# 4-USB_SATA.net
KiCad netlist of a schematic drawn in Altium Designer
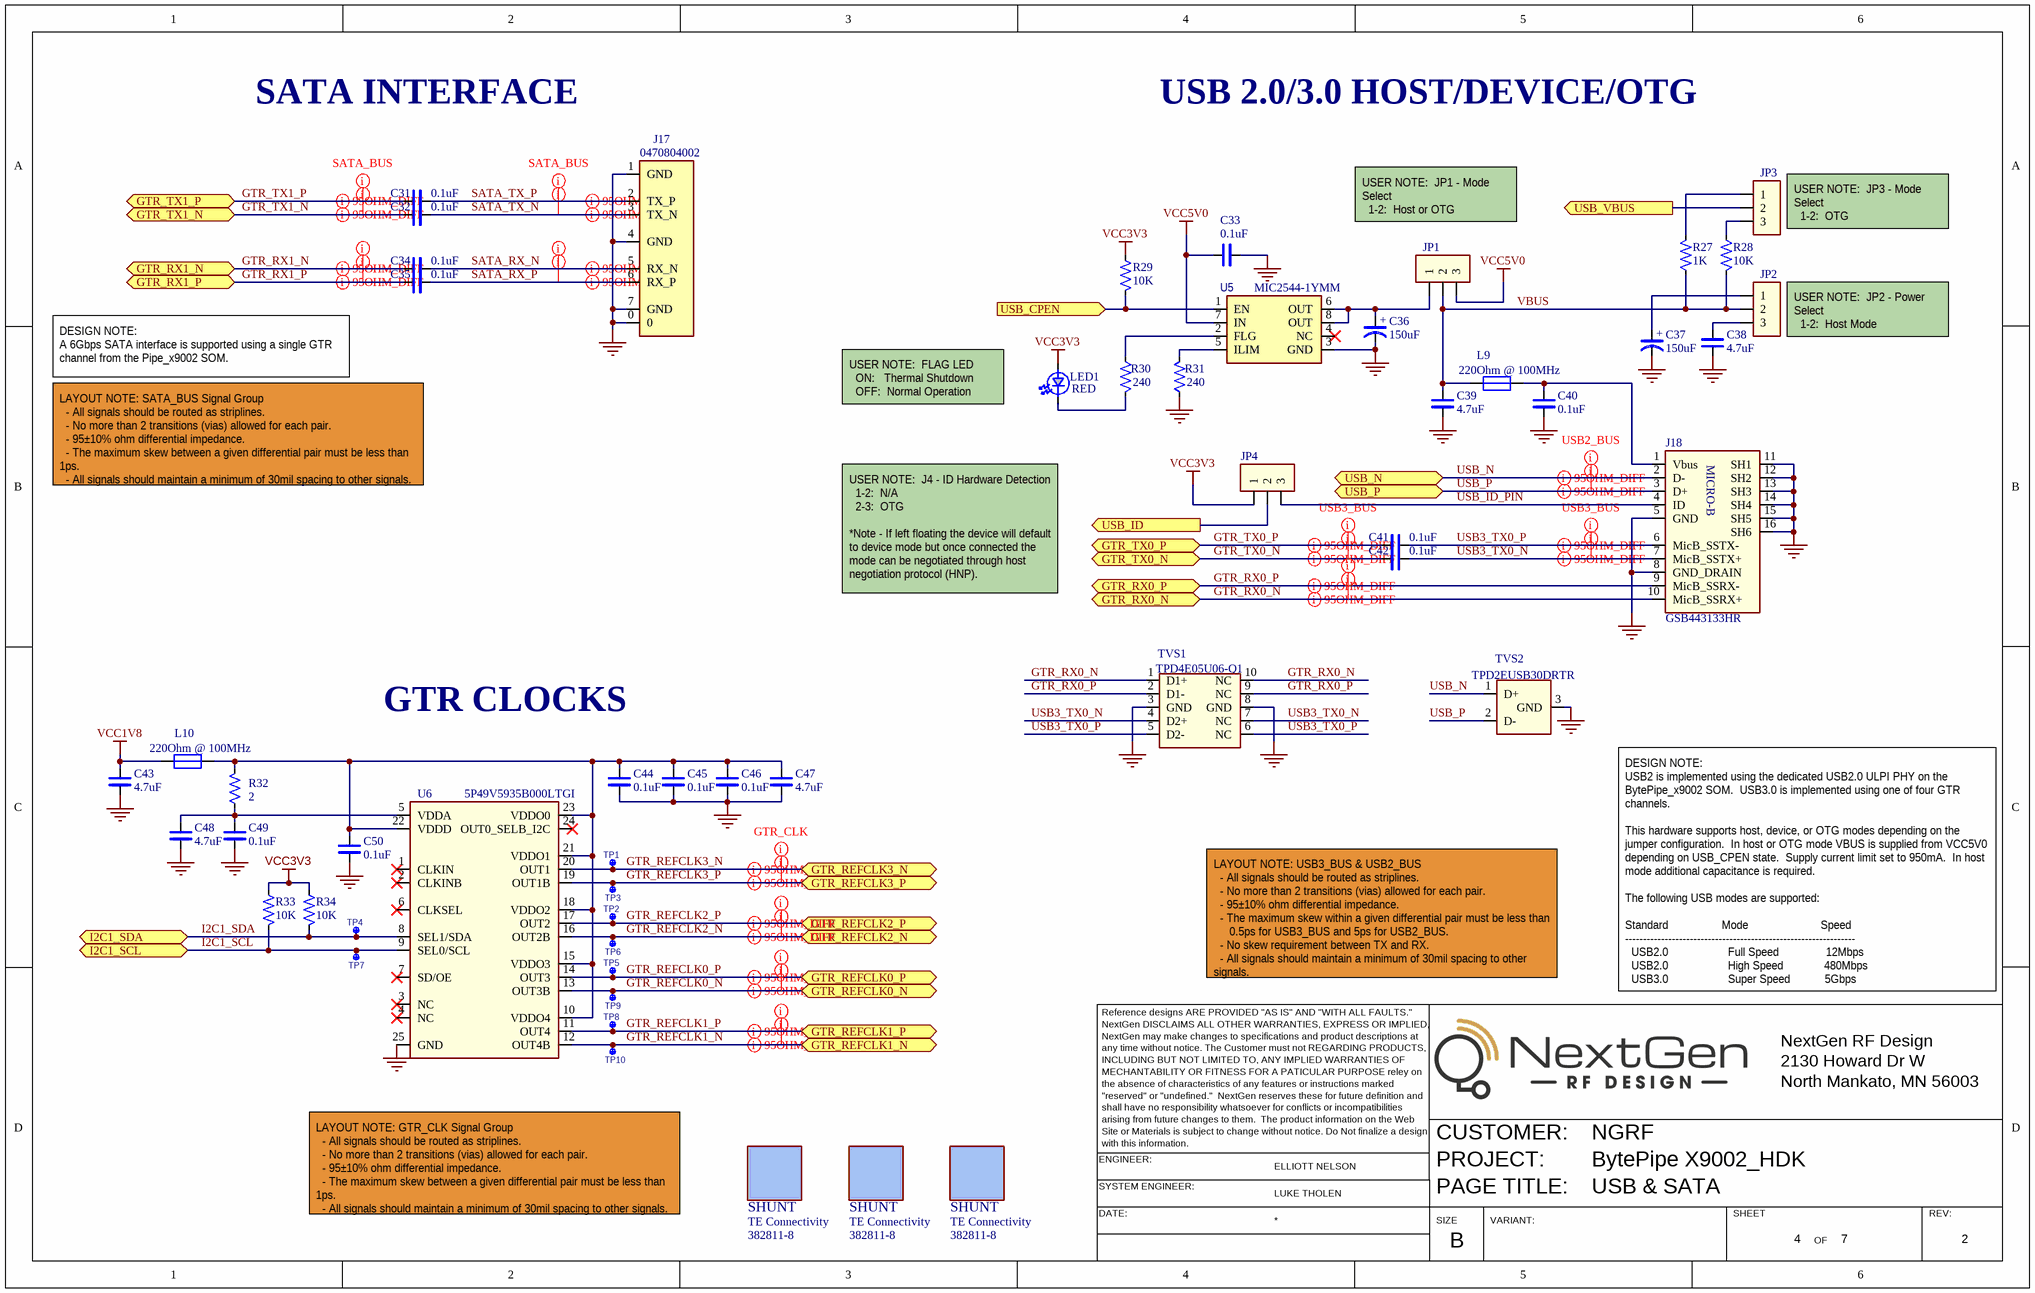
[diagram p0: 4-USB & SATA.SchDoc]

(export (version "E")
  (design (tool "Eeschema 10.0.6"))
  (components
    (comp (ref "C31")
      (value "0.1uF")
      (footprint "SM/0402/CAP")
      (description "CAP CER 0.1UF 25V X7R 0402")
      (fields (field (name "Comment") "CAP_CERAMIC_0402"))
      (libsource (lib "NextGenRF_Symbols_SMT") (part "CAP_CERAMIC_0402"))
    )
    (comp (ref "C32")
      (value "0.1uF")
      (footprint "SM/0402/CAP")
      (description "CAP CER 0.1UF 25V X7R 0402")
      (fields (field (name "Comment") "CAP_CERAMIC_0402"))
      (libsource (lib "NextGenRF_Symbols_SMT") (part "CAP_CERAMIC_0402"))
    )
    (comp (ref "C33")
      (value "0.1uF")
      (footprint "SM/0402/CAP")
      (description "CAP CER 0.1UF 25V X7R 0402")
      (fields (field (name "Comment") "CAP_CERAMIC_0402"))
      (libsource (lib "NextGenRF_Symbols_SMT") (part "CAP_CERAMIC_0402"))
    )
    (comp (ref "C34")
      (value "0.1uF")
      (footprint "SM/0402/CAP")
      (description "CAP CER 0.1UF 25V X7R 0402")
      (fields (field (name "Comment") "CAP_CERAMIC_0402"))
      (libsource (lib "NextGenRF_Symbols_SMT") (part "CAP_CERAMIC_0402"))
    )
    (comp (ref "C35")
      (value "0.1uF")
      (footprint "SM/0402/CAP")
      (description "CAP CER 0.1UF 25V X7R 0402")
      (fields (field (name "Comment") "CAP_CERAMIC_0402"))
      (libsource (lib "NextGenRF_Symbols_SMT") (part "CAP_CERAMIC_0402"))
    )
    (comp (ref "C36")
      (value "150uF")
      (footprint "NGRF_SMT_Footprints:SM/CAP/TANT-D_A")
      (description "CAP TANT 150UF 20% 10V 2917")
      (fields (field (name "Comment") "TANT-D"))
      (libsource (lib "NextGenRF_Symbols_SMT") (part "CAP_TANT-D"))
    )
    (comp (ref "C37")
      (value "150uF")
      (footprint "NGRF_SMT_Footprints:SM/CAP/TANT-D_A")
      (description "CAP TANT 150UF 20% 10V 2917")
      (fields (field (name "Comment") "TANT-D"))
      (libsource (lib "NextGenRF_Symbols_SMT") (part "CAP_TANT-D"))
    )
    (comp (ref "C38")
      (value "4.7uF")
      (footprint "SM/0402/CAP")
      (description "CAP CER 4.7UF 10V X5R 0402")
      (fields (field (name "Comment") "CAP_CERAMIC_0402"))
      (libsource (lib "NextGenRF_Symbols_SMT") (part "CAP_CERAMIC_0402"))
    )
    (comp (ref "C39")
      (value "4.7uF")
      (footprint "SM/0402/CAP")
      (description "CAP CER 4.7UF 10V X5R 0402")
      (fields (field (name "Comment") "CAP_CERAMIC_0402"))
      (libsource (lib "NextGenRF_Symbols_SMT") (part "CAP_CERAMIC_0402"))
    )
    (comp (ref "C40")
      (value "0.1uF")
      (footprint "SM/0402/CAP")
      (description "CAP CER 0.1UF 25V X7R 0402")
      (fields (field (name "Comment") "CAP_CERAMIC_0402"))
      (libsource (lib "NextGenRF_Symbols_SMT") (part "CAP_CERAMIC_0402"))
    )
    (comp (ref "C41")
      (value "0.1uF")
      (footprint "SM/0402/CAP")
      (description "CAP CER 0.1UF 25V X7R 0402")
      (fields (field (name "Comment") "CAP_CERAMIC_0402"))
      (libsource (lib "NextGenRF_Symbols_SMT") (part "CAP_CERAMIC_0402"))
    )
    (comp (ref "C42")
      (value "0.1uF")
      (footprint "SM/0402/CAP")
      (description "CAP CER 0.1UF 25V X7R 0402")
      (fields (field (name "Comment") "CAP_CERAMIC_0402"))
      (libsource (lib "NextGenRF_Symbols_SMT") (part "CAP_CERAMIC_0402"))
    )
    (comp (ref "C43")
      (value "4.7uF")
      (footprint "SM/0402/CAP")
      (description "CAP CER 4.7UF 10V X5R 0402")
      (fields (field (name "Comment") "CAP_CERAMIC_0402"))
      (libsource (lib "NextGenRF_Symbols_SMT") (part "CAP_CERAMIC_0402"))
    )
    (comp (ref "C44")
      (value "0.1uF")
      (footprint "SM/0402/CAP")
      (description "CAP CER 0.1UF 25V X7R 0402")
      (fields (field (name "Comment") "CAP_CERAMIC_0402"))
      (libsource (lib "NextGenRF_Symbols_SMT") (part "CAP_CERAMIC_0402"))
    )
    (comp (ref "C45")
      (value "0.1uF")
      (footprint "SM/0402/CAP")
      (description "CAP CER 0.1UF 25V X7R 0402")
      (fields (field (name "Comment") "CAP_CERAMIC_0402"))
      (libsource (lib "NextGenRF_Symbols_SMT") (part "CAP_CERAMIC_0402"))
    )
    (comp (ref "C46")
      (value "0.1uF")
      (footprint "SM/0402/CAP")
      (description "CAP CER 0.1UF 25V X7R 0402")
      (fields (field (name "Comment") "CAP_CERAMIC_0402"))
      (libsource (lib "NextGenRF_Symbols_SMT") (part "CAP_CERAMIC_0402"))
    )
    (comp (ref "C47")
      (value "4.7uF")
      (footprint "SM/0402/CAP")
      (description "CAP CER 4.7UF 10V X5R 0402")
      (fields (field (name "Comment") "CAP_CERAMIC_0402"))
      (libsource (lib "NextGenRF_Symbols_SMT") (part "CAP_CERAMIC_0402"))
    )
    (comp (ref "C48")
      (value "4.7uF")
      (footprint "SM/0402/CAP")
      (description "CAP CER 4.7UF 10V X5R 0402")
      (fields (field (name "Comment") "CAP_CERAMIC_0402"))
      (libsource (lib "NextGenRF_Symbols_SMT") (part "CAP_CERAMIC_0402"))
    )
    (comp (ref "C49")
      (value "0.1uF")
      (footprint "SM/0402/CAP")
      (description "CAP CER 0.1UF 25V X7R 0402")
      (fields (field (name "Comment") "CAP_CERAMIC_0402"))
      (libsource (lib "NextGenRF_Symbols_SMT") (part "CAP_CERAMIC_0402"))
    )
    (comp (ref "C50")
      (value "0.1uF")
      (footprint "SM/0402/CAP")
      (description "CAP CER 0.1UF 25V X7R 0402")
      (fields (field (name "Comment") "CAP_CERAMIC_0402"))
      (libsource (lib "NextGenRF_Symbols_SMT") (part "CAP_CERAMIC_0402"))
    )
    (comp (ref "J17")
      (value "0470804002")
      (footprint "SM/CON/MLX/SATA/0470804002")
      (description "7 Position SATA Plug Connector Solder Surface Mount, Right Angle")
      (fields (field (name "Comment") "CON_MOLEX_0470804002"))
      (libsource (lib "NextGenRF_Symbols_SMT") (part "CON_MOLEX_0470804002"))
    )
    (comp (ref "J18")
      (value "GSB443133HR")
      (footprint "SM/CON/USB3.1/MICRO B")
      (description "CONN RCPT USB3.1 MICRO B SMD R/A")
      (fields (field (name "Comment") "CON_USB_3.1_MICRO-B_RA"))
      (libsource (lib "NextGenRF_Symbols_SMT") (part "CON_USB_3.1_MICRO-B_RA"))
    )
    (comp (ref "JP1")
      (value "CON_100SP_1X3P_038H")
      (footprint "CON/100SP/1X3P")
      (description "PIN HEADER, SINGLE ROW 3 PIN STR")
      (libsource (lib "") (part "CON_100SP_1X3P_038H_1"))
    )
    (comp (ref "JP2")
      (value "CON_100SP_1X3P_038H")
      (footprint "CON/100SP/1X3P")
      (description "PIN HEADER, SINGLE ROW 3 PIN STR")
      (libsource (lib "NextGenRF_Symbols_TH") (part "CON_100SP_1X3P_038H"))
    )
    (comp (ref "JP3")
      (value "CON_100SP_1X3P_038H")
      (footprint "CON/100SP/1X3P")
      (description "PIN HEADER, SINGLE ROW 3 PIN STR")
      (libsource (lib "NextGenRF_Symbols_TH") (part "CON_100SP_1X3P_038H"))
    )
    (comp (ref "JP4")
      (value "CON_100SP_1X3P_038H")
      (footprint "CON/100SP/1X3P")
      (description "PIN HEADER, SINGLE ROW 3 PIN STR")
      (libsource (lib "") (part "CON_100SP_1X3P_038H_1"))
    )
    (comp (ref "L9")
      (value "220Ohm @ 100MHz")
      (footprint "NGRF_SMT_Footprints:SM/0603")
      (description "120 Ohms @ 100MHz 1 Power Line Ferrite Bead 0603 (1608 Metric) 3A 25mOhm")
      (fields (field (name "Comment") "FERRITE_0603_A"))
      (libsource (lib "NextGenRF_Symbols_SMT") (part "FERRITE_0603_A"))
    )
    (comp (ref "L10")
      (value "220Ohm @ 100MHz")
      (footprint "NGRF_SMT_Footprints:SM/0603")
      (description "120 Ohms @ 100MHz 1 Power Line Ferrite Bead 0603 (1608 Metric) 3A 25mOhm")
      (fields (field (name "Comment") "FERRITE_0603_A"))
      (libsource (lib "NextGenRF_Symbols_SMT") (part "FERRITE_0603_A"))
    )
    (comp (ref "LED1")
      (value "RED")
      (footprint "NGRF_SMT_Footprints:SM/LED_0603")
      (description "LED-0603")
      (fields (field (name "Comment") "LED_0603"))
      (libsource (lib "NextGenRF_Symbols_SMT") (part "LED_0603"))
    )
    (comp (ref "R27")
      (value "1K")
      (footprint "SM/0402/RES")
      (description "RES SMD 1K OHM 1% 1/10W 0402")
      (fields (field (name "Comment") "RES_0402_A"))
      (libsource (lib "NextGenRF_Symbols_SMT") (part "RES_0402_A"))
    )
    (comp (ref "R28")
      (value "10K")
      (footprint "SM/0402/RES")
      (fields (field (name "Comment") "RES_0402_A"))
      (libsource (lib "NextGenRF_Symbols_SMT") (part "RES_0402_A"))
    )
    (comp (ref "R29")
      (value "10K")
      (footprint "SM/0402/RES")
      (fields (field (name "Comment") "RES_0402_A"))
      (libsource (lib "NextGenRF_Symbols_SMT") (part "RES_0402_A"))
    )
    (comp (ref "R30")
      (value "240")
      (footprint "SM/0402/RES")
      (description "RES SMD 240 OHM 1% 1/10W 0402")
      (fields (field (name "Comment") "RES_0402_A"))
      (libsource (lib "NextGenRF_Symbols_SMT") (part "RES_0402_A"))
    )
    (comp (ref "R31")
      (value "240")
      (footprint "SM/0402/RES")
      (description "RES SMD 240 OHM 1% 1/10W 0402")
      (fields (field (name "Comment") "RES_0402_A"))
      (libsource (lib "NextGenRF_Symbols_SMT") (part "RES_0402_A"))
    )
    (comp (ref "R32")
      (value "2")
      (footprint "SM/0402/RES")
      (description "RES 2 OHM 1% 1/10W 0402 SMD")
      (fields (field (name "Comment") "RES_0402_A"))
      (libsource (lib "NextGenRF_Symbols_SMT") (part "RES_0402_A"))
    )
    (comp (ref "R33")
      (value "10K")
      (footprint "SM/0402/RES")
      (fields (field (name "Comment") "RES_0402_A"))
      (libsource (lib "NextGenRF_Symbols_SMT") (part "RES_0402_A"))
    )
    (comp (ref "R34")
      (value "10K")
      (footprint "SM/0402/RES")
      (fields (field (name "Comment") "RES_0402_A"))
      (libsource (lib "NextGenRF_Symbols_SMT") (part "RES_0402_A"))
    )
    (comp (ref "S1")
      (value "SHUNT")
      (fields (field (name "OEM NAME") "TE Connectivity") (field (name "OEM#") "382811-8"))
      (libsource (lib "NextGenRF_Symbols_MECH") (part "BOM_COMPONENT_NO-FOOTPRINT"))
    )
    (comp (ref "S2")
      (value "SHUNT")
      (fields (field (name "OEM NAME") "TE Connectivity") (field (name "OEM#") "382811-8"))
      (libsource (lib "NextGenRF_Symbols_MECH") (part "BOM_COMPONENT_NO-FOOTPRINT"))
    )
    (comp (ref "S3")
      (value "SHUNT")
      (fields (field (name "OEM NAME") "TE Connectivity") (field (name "OEM#") "382811-8"))
      (libsource (lib "NextGenRF_Symbols_MECH") (part "BOM_COMPONENT_NO-FOOTPRINT"))
    )
    (comp (ref "TP1")
      (value "TESTPOINT_030")
      (footprint "SM/TESTPOINT/30MIL")
      (libsource (lib "NextGenRF_Symbols_SMT") (part "TESTPOINT_030"))
    )
    (comp (ref "TP2")
      (value "TESTPOINT_030")
      (footprint "SM/TESTPOINT/30MIL")
      (libsource (lib "NextGenRF_Symbols_SMT") (part "TESTPOINT_030"))
    )
    (comp (ref "TP3")
      (value "TESTPOINT_030")
      (footprint "SM/TESTPOINT/30MIL")
      (libsource (lib "NextGenRF_Symbols_SMT") (part "TESTPOINT_030"))
    )
    (comp (ref "TP4")
      (value "TESTPOINT_030")
      (footprint "SM/TESTPOINT/30MIL")
      (libsource (lib "NextGenRF_Symbols_SMT") (part "TESTPOINT_030"))
    )
    (comp (ref "TP5")
      (value "TESTPOINT_030")
      (footprint "SM/TESTPOINT/30MIL")
      (libsource (lib "NextGenRF_Symbols_SMT") (part "TESTPOINT_030"))
    )
    (comp (ref "TP6")
      (value "TESTPOINT_030")
      (footprint "SM/TESTPOINT/30MIL")
      (libsource (lib "NextGenRF_Symbols_SMT") (part "TESTPOINT_030"))
    )
    (comp (ref "TP7")
      (value "TESTPOINT_030")
      (footprint "SM/TESTPOINT/30MIL")
      (libsource (lib "NextGenRF_Symbols_SMT") (part "TESTPOINT_030"))
    )
    (comp (ref "TP8")
      (value "TESTPOINT_030")
      (footprint "SM/TESTPOINT/30MIL")
      (libsource (lib "NextGenRF_Symbols_SMT") (part "TESTPOINT_030"))
    )
    (comp (ref "TP9")
      (value "TESTPOINT_030")
      (footprint "SM/TESTPOINT/30MIL")
      (libsource (lib "NextGenRF_Symbols_SMT") (part "TESTPOINT_030"))
    )
    (comp (ref "TP10")
      (value "TESTPOINT_030")
      (footprint "SM/TESTPOINT/30MIL")
      (libsource (lib "NextGenRF_Symbols_SMT") (part "TESTPOINT_030"))
    )
    (comp (ref "TVS1")
      (value "TPD4E05U06-Q1")
      (footprint "SM/DFN10/2.5X1MM_A")
      (description "TVS DIODE 5.5V 14V 10SON")
      (fields (field (name "Comment") "TVS_TPD4E05U06_2.5mmX1mm"))
      (libsource (lib "NextGenRF_Symbols_SMT") (part "TVS_TPD4E05U06_2.5mmX1mm"))
    )
    (comp (ref "TVS2")
      (value "TPD2EUSB30DRTR")
      (footprint "SM/SOT3_A")
      (description "TVS DIODE 5.5V 8V SOT3")
      (fields (field (name "Comment") "TVS_TPD2EUSB30DRTR_SOT3"))
      (libsource (lib "NextGenRF_Symbols_SMT") (part "TVS_TPD2EUSB30DRTR_SOT3"))
    )
    (comp (ref "U5")
      (value "MIC2544-1YMM")
      (footprint "SM/MSOP8_A")
      (description "Power Switch/Driver 1:1 N-Channel 1.5A 8-MSOP")
      (fields (field (name "Comment") "IC_MIC2544-1YMM_MSOP-8"))
      (libsource (lib "NextGenRF_Symbols_SMT") (part "IC_MIC2544-1YMM_MSOP-8"))
    )
    (comp (ref "U6")
      (value "5P49V5935B000LTGI")
      (footprint "SM/LGA24/4X4/0.5LS_A")
      (description "IC Programable Clock Generator")
      (fields (field (name "Comment") "IC_5P49V5935_LGA-24"))
      (libsource (lib "NextGenRF_Symbols_SMT") (part "IC_5P49V5935_LGA-24"))
    )
  )
  (nets
    (net (code "1") (name "/GTR_REFCLK0_N") (class "Default")
      (node (ref "TP9") (pin "1") (pinfunction "N1_1") (pintype "passive"))
      (node (ref "U6") (pin "13") (pinfunction "OUT3B_13") (pintype "passive"))
    )
    (net (code "2") (name "/GTR_REFCLK0_P") (class "Default")
      (node (ref "TP5") (pin "1") (pinfunction "N1_1") (pintype "passive"))
      (node (ref "U6") (pin "14") (pinfunction "OUT3_14") (pintype "passive"))
    )
    (net (code "3") (name "/GTR_REFCLK1_N") (class "Default")
      (node (ref "TP10") (pin "1") (pinfunction "N1_1") (pintype "passive"))
      (node (ref "U6") (pin "12") (pinfunction "OUT4B_12") (pintype "passive"))
    )
    (net (code "4") (name "/GTR_REFCLK1_P") (class "Default")
      (node (ref "TP8") (pin "1") (pinfunction "N1_1") (pintype "passive"))
      (node (ref "U6") (pin "11") (pinfunction "OUT4_11") (pintype "passive"))
    )
    (net (code "5") (name "/GTR_REFCLK2_N") (class "Default")
      (node (ref "TP6") (pin "1") (pinfunction "N1_1") (pintype "passive"))
      (node (ref "U6") (pin "16") (pinfunction "OUT2B_16") (pintype "passive"))
    )
    (net (code "6") (name "/GTR_REFCLK2_P") (class "Default")
      (node (ref "TP2") (pin "1") (pinfunction "N1_1") (pintype "passive"))
      (node (ref "U6") (pin "17") (pinfunction "OUT2_17") (pintype "passive"))
    )
    (net (code "7") (name "/GTR_REFCLK3_N") (class "Default")
      (node (ref "TP1") (pin "1") (pinfunction "N1_1") (pintype "passive"))
      (node (ref "U6") (pin "20") (pinfunction "OUT1_20") (pintype "passive"))
    )
    (net (code "8") (name "/GTR_REFCLK3_P") (class "Default")
      (node (ref "TP3") (pin "1") (pinfunction "N1_1") (pintype "passive"))
      (node (ref "U6") (pin "19") (pinfunction "OUT1B_19") (pintype "passive"))
    )
    (net (code "9") (name "/GTR_RX0_N") (class "Default")
      (node (ref "J18") (pin "10") (pinfunction "MicB_SSRX+_10") (pintype "passive"))
      (node (ref "TVS1") (pin "1") (pinfunction "D1+_1") (pintype "passive"))
      (node (ref "TVS1") (pin "10") (pinfunction "NC_10") (pintype "passive"))
    )
    (net (code "10") (name "/GTR_RX0_P") (class "Default")
      (node (ref "J18") (pin "9") (pinfunction "MicB_SSRX-_9") (pintype "passive"))
      (node (ref "TVS1") (pin "2") (pinfunction "D1-_2") (pintype "passive"))
      (node (ref "TVS1") (pin "9") (pinfunction "NC_9") (pintype "passive"))
    )
    (net (code "11") (name "/GTR_RX1_N") (class "Default")
      (node (ref "C34") (pin "1") (pinfunction "N1_1") (pintype "passive"))
    )
    (net (code "12") (name "/GTR_RX1_P") (class "Default")
      (node (ref "C35") (pin "1") (pinfunction "N1_1") (pintype "passive"))
    )
    (net (code "13") (name "/GTR_TX0_N") (class "Default")
      (node (ref "C42") (pin "1") (pinfunction "N1_1") (pintype "passive"))
    )
    (net (code "14") (name "/GTR_TX0_P") (class "Default")
      (node (ref "C41") (pin "1") (pinfunction "N1_1") (pintype "passive"))
    )
    (net (code "15") (name "/GTR_TX1_N") (class "Default")
      (node (ref "C32") (pin "1") (pinfunction "N1_1") (pintype "passive"))
    )
    (net (code "16") (name "/GTR_TX1_P") (class "Default")
      (node (ref "C31") (pin "1") (pinfunction "N1_1") (pintype "passive"))
    )
    (net (code "17") (name "/I2C1_SCL") (class "Default")
      (node (ref "R33") (pin "2") (pinfunction "2_2") (pintype "passive"))
      (node (ref "TP7") (pin "1") (pinfunction "N1_1") (pintype "passive"))
      (node (ref "U6") (pin "9") (pinfunction "SEL0/SCL_9") (pintype "passive"))
    )
    (net (code "18") (name "/I2C1_SDA") (class "Default")
      (node (ref "R34") (pin "2") (pinfunction "2_2") (pintype "passive"))
      (node (ref "TP4") (pin "1") (pinfunction "N1_1") (pintype "passive"))
      (node (ref "U6") (pin "8") (pinfunction "SEL1/SDA_8") (pintype "passive"))
    )
    (net (code "19") (name "/SATA_RX_N") (class "Default")
      (node (ref "C34") (pin "2") (pinfunction "N2_2") (pintype "passive"))
      (node (ref "J17") (pin "5") (pinfunction "RX_N_5") (pintype "passive"))
    )
    (net (code "20") (name "/SATA_RX_P") (class "Default")
      (node (ref "C35") (pin "2") (pinfunction "N2_2") (pintype "passive"))
      (node (ref "J17") (pin "6") (pinfunction "RX_P_6") (pintype "passive"))
    )
    (net (code "21") (name "/SATA_TX_N") (class "Default")
      (node (ref "C32") (pin "2") (pinfunction "N2_2") (pintype "passive"))
      (node (ref "J17") (pin "3") (pinfunction "TX_N_3") (pintype "passive"))
    )
    (net (code "22") (name "/SATA_TX_P") (class "Default")
      (node (ref "C31") (pin "2") (pinfunction "N2_2") (pintype "passive"))
      (node (ref "J17") (pin "2") (pinfunction "TX_P_2") (pintype "passive"))
    )
    (net (code "23") (name "/USB3_TX0_N") (class "Default")
      (node (ref "C42") (pin "2") (pinfunction "N2_2") (pintype "passive"))
      (node (ref "J18") (pin "7") (pinfunction "MicB_SSTX+_7") (pintype "passive"))
      (node (ref "TVS1") (pin "4") (pinfunction "D2+_4") (pintype "passive"))
      (node (ref "TVS1") (pin "7") (pinfunction "NC_7") (pintype "passive"))
    )
    (net (code "24") (name "/USB3_TX0_P") (class "Default")
      (node (ref "C41") (pin "2") (pinfunction "N2_2") (pintype "passive"))
      (node (ref "J18") (pin "6") (pinfunction "MicB_SSTX-_6") (pintype "passive"))
      (node (ref "TVS1") (pin "5") (pinfunction "D2-_5") (pintype "passive"))
      (node (ref "TVS1") (pin "6") (pinfunction "NC_6") (pintype "passive"))
    )
    (net (code "25") (name "/USB_CPEN") (class "Default")
      (node (ref "R29") (pin "2") (pinfunction "2_2") (pintype "passive"))
      (node (ref "U5") (pin "1") (pinfunction "EN_1") (pintype "passive"))
    )
    (net (code "26") (name "/USB_ID") (class "Default")
      (node (ref "JP4") (pin "2") (pinfunction "2_2") (pintype "passive"))
    )
    (net (code "27") (name "/USB_ID_PIN") (class "Default")
      (node (ref "J18") (pin "4") (pinfunction "ID_4") (pintype "passive"))
      (node (ref "JP4") (pin "3") (pinfunction "3_3") (pintype "passive"))
    )
    (net (code "28") (name "/USB_N") (class "Default")
      (node (ref "J18") (pin "2") (pinfunction "D-_2") (pintype "passive"))
      (node (ref "TVS2") (pin "1") (pinfunction "D+_1") (pintype "passive"))
    )
    (net (code "29") (name "/USB_P") (class "Default")
      (node (ref "J18") (pin "3") (pinfunction "D+_3") (pintype "passive"))
      (node (ref "TVS2") (pin "2") (pinfunction "D-_2") (pintype "passive"))
    )
    (net (code "30") (name "/USB_VBUS") (class "Default")
      (node (ref "JP3") (pin "2") (pinfunction "2_2") (pintype "passive"))
    )
    (net (code "31") (name "/VBUS") (class "Default")
      (node (ref "C39") (pin "1") (pinfunction "N1_1") (pintype "passive"))
      (node (ref "JP1") (pin "2") (pinfunction "2_2") (pintype "passive"))
      (node (ref "JP2") (pin "2") (pinfunction "2_2") (pintype "passive"))
      (node (ref "L9") (pin "1") (pinfunction "PIN1_1") (pintype "passive"))
      (node (ref "R27") (pin "1") (pinfunction "1_1") (pintype "passive"))
      (node (ref "R28") (pin "2") (pinfunction "2_2") (pintype "passive"))
    )
    (net (code "32") (name "GND") (class "Default")
      (node (ref "C33") (pin "2") (pinfunction "N2_2") (pintype "passive"))
      (node (ref "C36") (pin "2") (pinfunction "N_2") (pintype "passive"))
      (node (ref "C37") (pin "2") (pinfunction "N_2") (pintype "passive"))
      (node (ref "C38") (pin "2") (pinfunction "N2_2") (pintype "passive"))
      (node (ref "C39") (pin "2") (pinfunction "N2_2") (pintype "passive"))
      (node (ref "C40") (pin "2") (pinfunction "N2_2") (pintype "passive"))
      (node (ref "C43") (pin "2") (pinfunction "N2_2") (pintype "passive"))
      (node (ref "C44") (pin "2") (pinfunction "N2_2") (pintype "passive"))
      (node (ref "C45") (pin "2") (pinfunction "N2_2") (pintype "passive"))
      (node (ref "C46") (pin "2") (pinfunction "N2_2") (pintype "passive"))
      (node (ref "C47") (pin "2") (pinfunction "N2_2") (pintype "passive"))
      (node (ref "C48") (pin "2") (pinfunction "N2_2") (pintype "passive"))
      (node (ref "C49") (pin "2") (pinfunction "N2_2") (pintype "passive"))
      (node (ref "C50") (pin "2") (pinfunction "N2_2") (pintype "passive"))
      (node (ref "J17") (pin "0") (pinfunction "0_0") (pintype "passive"))
      (node (ref "J17") (pin "1") (pinfunction "GND_1") (pintype "passive"))
      (node (ref "J17") (pin "4") (pinfunction "GND_4") (pintype "passive"))
      (node (ref "J17") (pin "7") (pinfunction "GND_7") (pintype "passive"))
      (node (ref "J18") (pin "11") (pinfunction "SH1_11") (pintype "passive"))
      (node (ref "J18") (pin "12") (pinfunction "SH2_12") (pintype "passive"))
      (node (ref "J18") (pin "13") (pinfunction "SH3_13") (pintype "passive"))
      (node (ref "J18") (pin "14") (pinfunction "SH4_14") (pintype "passive"))
      (node (ref "J18") (pin "15") (pinfunction "SH5_15") (pintype "passive"))
      (node (ref "J18") (pin "16") (pinfunction "SH6_16") (pintype "passive"))
      (node (ref "J18") (pin "5") (pinfunction "GND_5") (pintype "passive"))
      (node (ref "J18") (pin "8") (pinfunction "GND_DRAIN_8") (pintype "passive"))
      (node (ref "R31") (pin "2") (pinfunction "2_2") (pintype "passive"))
      (node (ref "TVS1") (pin "3") (pinfunction "GND_3") (pintype "passive"))
      (node (ref "TVS1") (pin "8") (pinfunction "GND_8") (pintype "passive"))
      (node (ref "TVS2") (pin "3") (pinfunction "GND_3") (pintype "passive"))
      (node (ref "U5") (pin "3") (pinfunction "GND_3") (pintype "passive"))
      (node (ref "U6") (pin "25") (pinfunction "GND_25") (pintype "passive"))
    )
    (net (code "33") (name "Net-(C36-+)") (class "Default")
      (node (ref "C36") (pin "1") (pinfunction "+_1") (pintype "passive"))
      (node (ref "JP1") (pin "1") (pinfunction "1_1") (pintype "passive"))
      (node (ref "U5") (pin "6") (pinfunction "OUT_6") (pintype "passive"))
      (node (ref "U5") (pin "8") (pinfunction "OUT_8") (pintype "passive"))
    )
    (net (code "34") (name "Net-(C37-+)") (class "Default")
      (node (ref "C37") (pin "1") (pinfunction "+_1") (pintype "passive"))
      (node (ref "JP2") (pin "1") (pinfunction "1_1") (pintype "passive"))
    )
    (net (code "35") (name "Net-(C38-N1)") (class "Default")
      (node (ref "C38") (pin "1") (pinfunction "N1_1") (pintype "passive"))
      (node (ref "JP2") (pin "3") (pinfunction "3_3") (pintype "passive"))
    )
    (net (code "36") (name "Net-(C40-N1)") (class "Default")
      (node (ref "C40") (pin "1") (pinfunction "N1_1") (pintype "passive"))
      (node (ref "J18") (pin "1") (pinfunction "Vbus_1") (pintype "passive"))
      (node (ref "L9") (pin "2") (pinfunction "PIN2_2") (pintype "passive"))
    )
    (net (code "37") (name "Net-(C44-N1)") (class "Default")
      (node (ref "C44") (pin "1") (pinfunction "N1_1") (pintype "passive"))
      (node (ref "C45") (pin "1") (pinfunction "N1_1") (pintype "passive"))
      (node (ref "C46") (pin "1") (pinfunction "N1_1") (pintype "passive"))
      (node (ref "C47") (pin "1") (pinfunction "N1_1") (pintype "passive"))
      (node (ref "C50") (pin "1") (pinfunction "N1_1") (pintype "passive"))
      (node (ref "L10") (pin "2") (pinfunction "PIN2_2") (pintype "passive"))
      (node (ref "R32") (pin "1") (pinfunction "1_1") (pintype "passive"))
      (node (ref "U6") (pin "10") (pinfunction "VDDO4_10") (pintype "passive"))
      (node (ref "U6") (pin "15") (pinfunction "VDDO3_15") (pintype "passive"))
      (node (ref "U6") (pin "18") (pinfunction "VDDO2_18") (pintype "passive"))
      (node (ref "U6") (pin "21") (pinfunction "VDDO1_21") (pintype "passive"))
      (node (ref "U6") (pin "22") (pinfunction "VDDD_22") (pintype "passive"))
      (node (ref "U6") (pin "23") (pinfunction "VDDO0_23") (pintype "passive"))
    )
    (net (code "38") (name "Net-(C48-N1)") (class "Default")
      (node (ref "C48") (pin "1") (pinfunction "N1_1") (pintype "passive"))
      (node (ref "C49") (pin "1") (pinfunction "N1_1") (pintype "passive"))
      (node (ref "R32") (pin "2") (pinfunction "2_2") (pintype "passive"))
      (node (ref "U6") (pin "5") (pinfunction "VDDA_5") (pintype "passive"))
    )
    (net (code "39") (name "Net-(JP3-Pad1)") (class "Default")
      (node (ref "JP3") (pin "1") (pinfunction "1_1") (pintype "passive"))
      (node (ref "R27") (pin "2") (pinfunction "2_2") (pintype "passive"))
    )
    (net (code "40") (name "Net-(JP3-Pad3)") (class "Default")
      (node (ref "JP3") (pin "3") (pinfunction "3_3") (pintype "passive"))
      (node (ref "R28") (pin "1") (pinfunction "1_1") (pintype "passive"))
    )
    (net (code "41") (name "Net-(LED1-C)") (class "Default")
      (node (ref "LED1") (pin "1") (pinfunction "C_1") (pintype "passive"))
      (node (ref "R30") (pin "1") (pinfunction "1_1") (pintype "passive"))
    )
    (net (code "42") (name "Net-(U5-FLG)") (class "Default")
      (node (ref "R30") (pin "2") (pinfunction "2_2") (pintype "passive"))
      (node (ref "U5") (pin "2") (pinfunction "FLG_2") (pintype "passive"))
    )
    (net (code "43") (name "Net-(U5-ILIM)") (class "Default")
      (node (ref "R31") (pin "1") (pinfunction "1_1") (pintype "passive"))
      (node (ref "U5") (pin "5") (pinfunction "ILIM_5") (pintype "passive"))
    )
    (net (code "44") (name "VCC1V8") (class "Default")
      (node (ref "C43") (pin "1") (pinfunction "N1_1") (pintype "passive"))
      (node (ref "L10") (pin "1") (pinfunction "PIN1_1") (pintype "passive"))
    )
    (net (code "45") (name "VCC3V3") (class "Default")
      (node (ref "JP4") (pin "1") (pinfunction "1_1") (pintype "passive"))
      (node (ref "LED1") (pin "2") (pinfunction "A_2") (pintype "passive"))
      (node (ref "R29") (pin "1") (pinfunction "1_1") (pintype "passive"))
      (node (ref "R33") (pin "1") (pinfunction "1_1") (pintype "passive"))
      (node (ref "R34") (pin "1") (pinfunction "1_1") (pintype "passive"))
    )
    (net (code "46") (name "VCC5V0") (class "Default")
      (node (ref "C33") (pin "1") (pinfunction "N1_1") (pintype "passive"))
      (node (ref "JP1") (pin "3") (pinfunction "3_3") (pintype "passive"))
      (node (ref "U5") (pin "7") (pinfunction "IN_7") (pintype "passive"))
    )
    (net (code "47") (name "unconnected-(U5-NC-Pad4)") (class "Default")
      (node (ref "U5") (pin "4") (pinfunction "NC_4") (pintype "passive+no_connect"))
    )
    (net (code "48") (name "unconnected-(U6-CLKIN-Pad1)") (class "Default")
      (node (ref "U6") (pin "1") (pinfunction "CLKIN_1") (pintype "passive+no_connect"))
    )
    (net (code "49") (name "unconnected-(U6-CLKINB-Pad2)") (class "Default")
      (node (ref "U6") (pin "2") (pinfunction "CLKINB_2") (pintype "passive+no_connect"))
    )
    (net (code "50") (name "unconnected-(U6-CLKSEL-Pad6)") (class "Default")
      (node (ref "U6") (pin "6") (pinfunction "CLKSEL_6") (pintype "passive+no_connect"))
    )
    (net (code "51") (name "unconnected-(U6-NC-Pad3)") (class "Default")
      (node (ref "U6") (pin "3") (pinfunction "NC_3") (pintype "passive+no_connect"))
    )
    (net (code "52") (name "unconnected-(U6-NC-Pad4)") (class "Default")
      (node (ref "U6") (pin "4") (pinfunction "NC_4") (pintype "passive+no_connect"))
    )
    (net (code "53") (name "unconnected-(U6-OUT0_SELB_I2C-Pad24)") (class "Default")
      (node (ref "U6") (pin "24") (pinfunction "OUT0_SELB_I2C_24") (pintype "passive+no_connect"))
    )
    (net (code "54") (name "unconnected-(U6-SD{slash}OE-Pad7)") (class "Default")
      (node (ref "U6") (pin "7") (pinfunction "SD/OE_7") (pintype "passive+no_connect"))
    )
  )
)
